# SCH_Front.net
KiCad netlist of a schematic drawn in Altium Designer
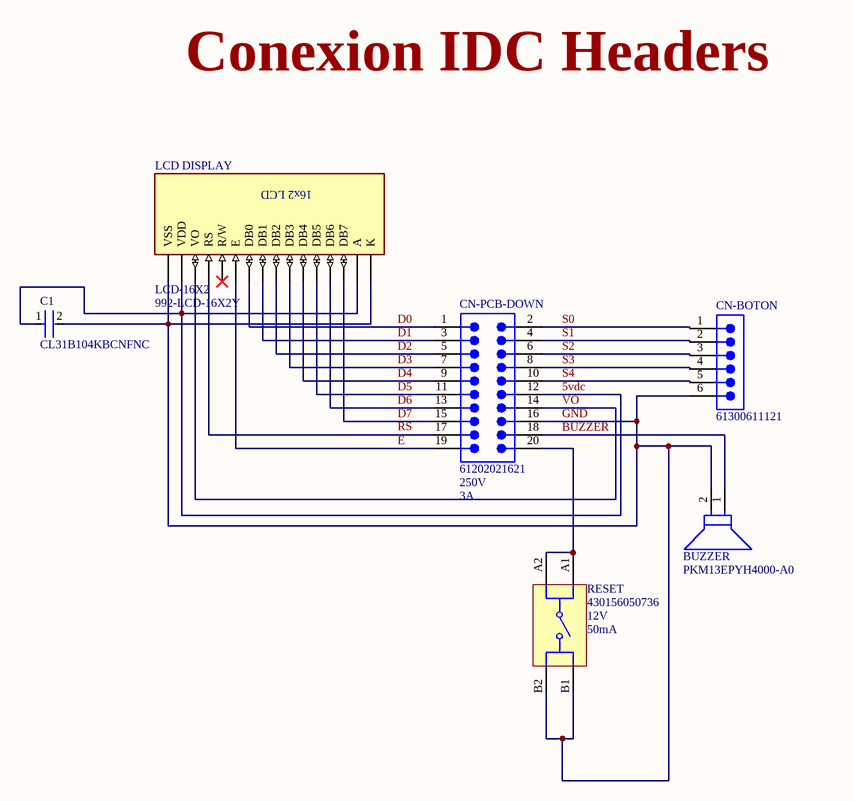
[diagram p0: SCH Front.SchDoc]

(export (version "E")
  (design (tool "Eeschema 10.0.6"))
  (components
    (comp (ref "BUZZER")
      (value "PKM13EPYH4000-A0")
      (footprint "FP-PKM13EPYH4000-A0-MFG")
      (description "AUDIO PIEZO TRANSDUCER 30V TH")
      (libsource (lib "Altium Content Vault") (part "5f581d31613f872430949aa526fd155"))
    )
    (comp (ref "C1")
      (value "CL31B104KBCNFNC")
      (footprint "FP-CL31-IPC_C")
      (description "Cap Ceramic 100nF 50V X7R ±10% SMD 1206 +125°C Embossed T/R")
      (fields (field (name "TOLERANCE") "10%"))
      (libsource (lib "Altium Content Vault") (part "b4654b650e69147ec39a6b967a45e02"))
    )
    (comp (ref "CN-BOTON")
      (value "61300611121")
      (footprint "61300611121")
      (libsource (lib "Altium Content Vault") (part "Header_Male_1R_06P"))
    )
    (comp (ref "CN-PCB-DOWN")
      (value "61202021621")
      (footprint "61202021621")
      (fields (field (name "VOLTAGE RATING (DC)") "250V") (field (name "CURRENT RATING") "3A"))
      (libsource (lib "Altium Content Vault") (part "Header_Male_2R_20P"))
    )
    (comp (ref "LCD DISPLAY")
      (value "LCD-16X2")
      (footprint "MODULE_LCD-16X2")
      (description "Display Development Tools 16x2 Black on Green Char LCD w Backlight")
      (fields
        (field (name "MF") "Gravitech")
        (field (name "MANUFACTURER PART NUMBER") "LCD-16X2Y")
        (field (name "SUPPLIER PART NUMBER 1") "992-LCD-16X2Y")
      )
      (libsource (lib "LCD-16X2") (part "LCD-16X2"))
    )
    (comp (ref "RESET")
      (value "430156050736")
      (footprint "4301x60507x6")
      (fields (field (name "VOLTAGE RATING") "12V") (field (name "CURRENT RATING") "50mA"))
      (libsource (lib "Altium Content Vault") (part "SPST-NO_4P"))
    )
  )
  (nets
    (net (code "1") (name "/5vdc") (class "Default")
      (node (ref "C1") (pin "1") (pinfunction "1_1") (pintype "passive"))
      (node (ref "CN-PCB-DOWN") (pin "12") (pinfunction "12_12") (pintype "passive"))
      (node (ref "LCD DISPLAY") (pin "15") (pinfunction "A_15") (pintype "power_in"))
      (node (ref "LCD DISPLAY") (pin "2") (pinfunction "VDD_2") (pintype "power_in"))
    )
    (net (code "2") (name "/BUZZER") (class "Default")
      (node (ref "BUZZER") (pin "1") (pinfunction "1_1") (pintype "passive"))
      (node (ref "CN-PCB-DOWN") (pin "18") (pinfunction "18_18") (pintype "passive"))
    )
    (net (code "3") (name "/D0") (class "Default")
      (node (ref "CN-PCB-DOWN") (pin "1") (pinfunction "1_1") (pintype "passive"))
      (node (ref "LCD DISPLAY") (pin "7") (pinfunction "DB0_7") (pintype "bidirectional"))
    )
    (net (code "4") (name "/D1") (class "Default")
      (node (ref "CN-PCB-DOWN") (pin "3") (pinfunction "3_3") (pintype "passive"))
      (node (ref "LCD DISPLAY") (pin "8") (pinfunction "DB1_8") (pintype "bidirectional"))
    )
    (net (code "5") (name "/D2") (class "Default")
      (node (ref "CN-PCB-DOWN") (pin "5") (pinfunction "5_5") (pintype "passive"))
      (node (ref "LCD DISPLAY") (pin "9") (pinfunction "DB2_9") (pintype "bidirectional"))
    )
    (net (code "6") (name "/D3") (class "Default")
      (node (ref "CN-PCB-DOWN") (pin "7") (pinfunction "7_7") (pintype "passive"))
      (node (ref "LCD DISPLAY") (pin "10") (pinfunction "DB3_10") (pintype "bidirectional"))
    )
    (net (code "7") (name "/D4") (class "Default")
      (node (ref "CN-PCB-DOWN") (pin "9") (pinfunction "9_9") (pintype "passive"))
      (node (ref "LCD DISPLAY") (pin "11") (pinfunction "DB4_11") (pintype "bidirectional"))
    )
    (net (code "8") (name "/D5") (class "Default")
      (node (ref "CN-PCB-DOWN") (pin "11") (pinfunction "11_11") (pintype "passive"))
      (node (ref "LCD DISPLAY") (pin "12") (pinfunction "DB5_12") (pintype "bidirectional"))
    )
    (net (code "9") (name "/D6") (class "Default")
      (node (ref "CN-PCB-DOWN") (pin "13") (pinfunction "13_13") (pintype "passive"))
      (node (ref "LCD DISPLAY") (pin "13") (pinfunction "DB6_13") (pintype "bidirectional"))
    )
    (net (code "10") (name "/D7") (class "Default")
      (node (ref "CN-PCB-DOWN") (pin "15") (pinfunction "15_15") (pintype "passive"))
      (node (ref "LCD DISPLAY") (pin "14") (pinfunction "DB7_14") (pintype "bidirectional"))
    )
    (net (code "11") (name "/E") (class "Default")
      (node (ref "CN-PCB-DOWN") (pin "19") (pinfunction "19_19") (pintype "passive"))
      (node (ref "LCD DISPLAY") (pin "6") (pinfunction "E_6") (pintype "input"))
    )
    (net (code "12") (name "/GND") (class "Default")
      (node (ref "BUZZER") (pin "2") (pinfunction "2_2") (pintype "passive"))
      (node (ref "C1") (pin "2") (pinfunction "2_2") (pintype "passive"))
      (node (ref "CN-BOTON") (pin "6") (pinfunction "6_6") (pintype "passive"))
      (node (ref "CN-PCB-DOWN") (pin "16") (pinfunction "16_16") (pintype "passive"))
      (node (ref "LCD DISPLAY") (pin "1") (pinfunction "VSS_1") (pintype "power_in"))
      (node (ref "LCD DISPLAY") (pin "16") (pinfunction "K_16") (pintype "power_in"))
      (node (ref "RESET") (pin "B1") (pinfunction "B1_B1") (pintype "passive"))
      (node (ref "RESET") (pin "B2") (pinfunction "B2_B2") (pintype "passive"))
    )
    (net (code "14") (name "/RS") (class "Default")
      (node (ref "CN-PCB-DOWN") (pin "17") (pinfunction "17_17") (pintype "passive"))
      (node (ref "LCD DISPLAY") (pin "4") (pinfunction "RS_4") (pintype "input"))
    )
    (net (code "15") (name "/S0") (class "Default")
      (node (ref "CN-BOTON") (pin "1") (pinfunction "1_1") (pintype "passive"))
      (node (ref "CN-PCB-DOWN") (pin "2") (pinfunction "2_2") (pintype "passive"))
    )
    (net (code "16") (name "/S1") (class "Default")
      (node (ref "CN-BOTON") (pin "2") (pinfunction "2_2") (pintype "passive"))
      (node (ref "CN-PCB-DOWN") (pin "4") (pinfunction "4_4") (pintype "passive"))
    )
    (net (code "17") (name "/S2") (class "Default")
      (node (ref "CN-BOTON") (pin "3") (pinfunction "3_3") (pintype "passive"))
      (node (ref "CN-PCB-DOWN") (pin "6") (pinfunction "6_6") (pintype "passive"))
    )
    (net (code "18") (name "/S3") (class "Default")
      (node (ref "CN-BOTON") (pin "4") (pinfunction "4_4") (pintype "passive"))
      (node (ref "CN-PCB-DOWN") (pin "8") (pinfunction "8_8") (pintype "passive"))
    )
    (net (code "19") (name "/S4") (class "Default")
      (node (ref "CN-BOTON") (pin "5") (pinfunction "5_5") (pintype "passive"))
      (node (ref "CN-PCB-DOWN") (pin "10") (pinfunction "10_10") (pintype "passive"))
    )
    (net (code "20") (name "/VO") (class "Default")
      (node (ref "CN-PCB-DOWN") (pin "14") (pinfunction "14_14") (pintype "passive"))
      (node (ref "LCD DISPLAY") (pin "3") (pinfunction "VO_3") (pintype "bidirectional"))
    )
    (net (code "21") (name "Net-(CN-PCB-DOWN-Pad20)") (class "Default")
      (node (ref "CN-PCB-DOWN") (pin "20") (pinfunction "20_20") (pintype "passive"))
      (node (ref "RESET") (pin "A1") (pinfunction "A1_A1") (pintype "passive"))
      (node (ref "RESET") (pin "A2") (pinfunction "A2_A2") (pintype "passive"))
    )
    (net (code "22") (name "unconnected-(LCD DISPLAY-R{slash}W-Pad5)") (class "Default")
      (node (ref "LCD DISPLAY") (pin "5") (pinfunction "R/W_5") (pintype "input+no_connect"))
    )
  )
)
